# Altium_Designer_schematic.net
KiCad netlist of a schematic drawn in Altium Designer
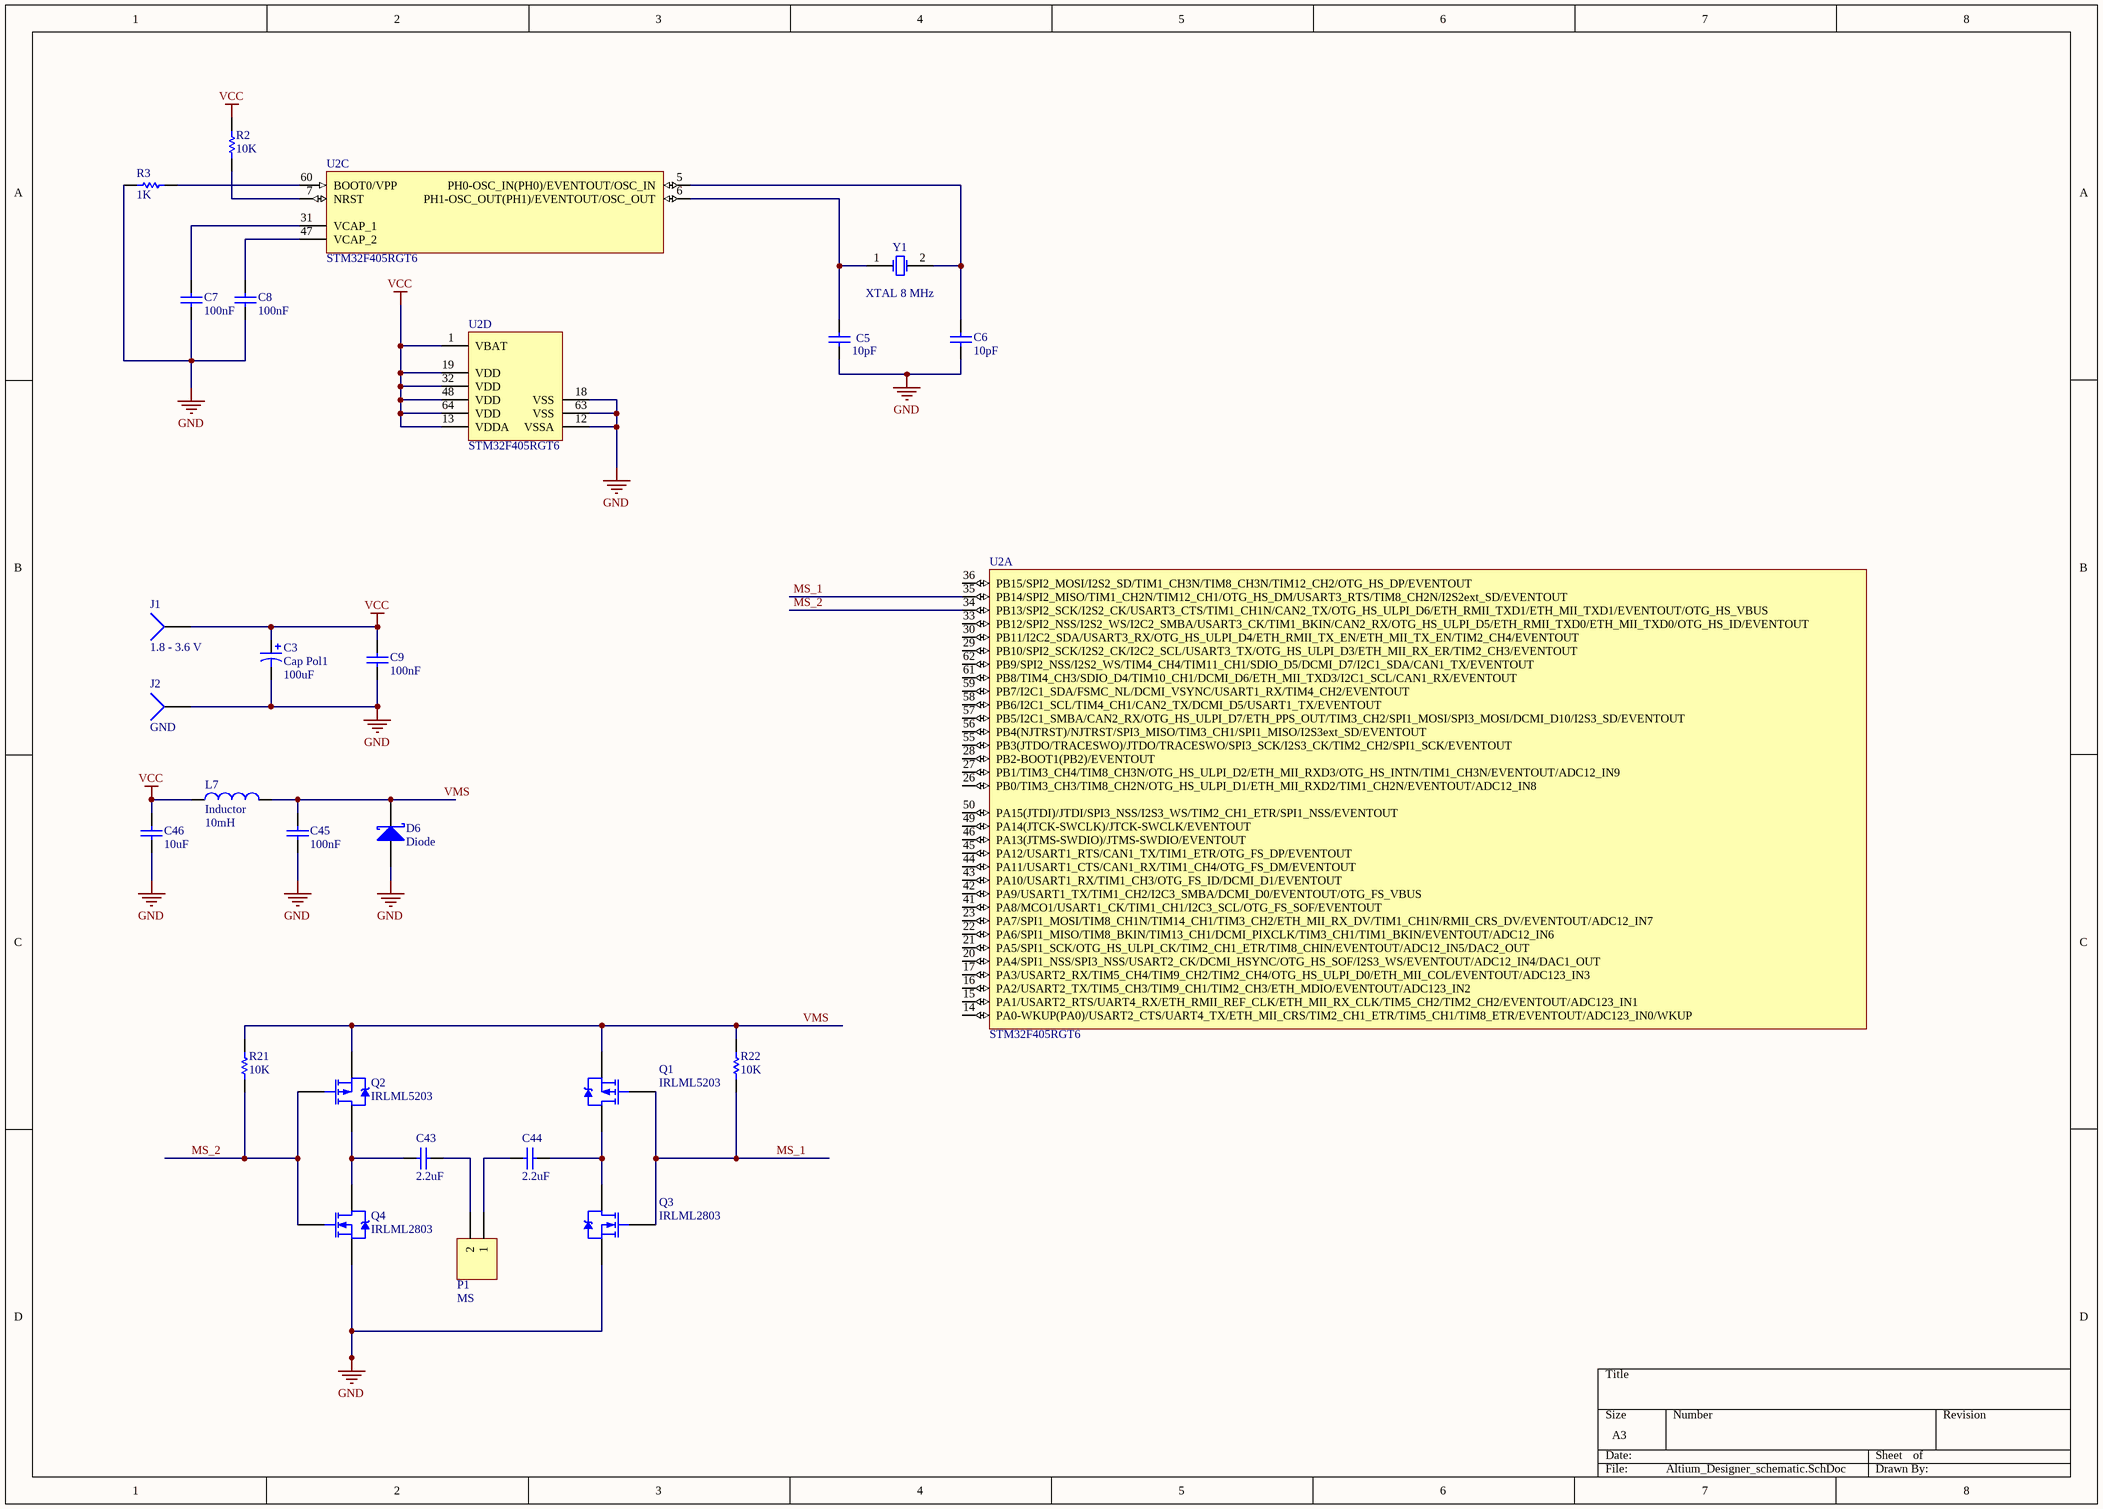
[diagram p0: Altium_Designer_schematic.SchDoc]

(export (version "E")
  (design (tool "Eeschema 10.0.6"))
  (components
    (comp (ref "C3")
      (value "Cap Pol1")
      (footprint "RB7.6-15")
      (description "Polarized Capacitor (Radial)")
      (fields (field (name "ALTIUM_VALUE") "100uF") (field (name "PUBLISHER") "Altium Limited"))
      (libsource (lib "Miscellaneous Devices") (part "Cap Pol1"))
    )
    (comp (ref "C5")
      (value "10pF")
      (footprint "Miscellaneous Devices:1-0805_N")
      (description "Capacitor")
      (fields (field (name "PUBLISHER") "Altium Limited"))
      (libsource (lib "Miscellaneous Devices") (part "Cap"))
    )
    (comp (ref "C6")
      (value "10pF")
      (footprint "Miscellaneous Devices:1-0805_N")
      (description "Capacitor")
      (fields (field (name "PUBLISHER") "Altium Limited"))
      (libsource (lib "Miscellaneous Devices") (part "Cap"))
    )
    (comp (ref "C7")
      (value "100nF")
      (footprint "Miscellaneous Devices:1-0805_N")
      (description "Capacitor")
      (fields (field (name "PUBLISHER") "Altium Limited"))
      (libsource (lib "Miscellaneous Devices") (part "Cap"))
    )
    (comp (ref "C8")
      (value "100nF")
      (footprint "Miscellaneous Devices:1-0805_N")
      (description "Capacitor")
      (fields (field (name "PUBLISHER") "Altium Limited"))
      (libsource (lib "Miscellaneous Devices") (part "Cap"))
    )
    (comp (ref "C9")
      (value "100nF")
      (footprint "Miscellaneous Devices:1-0805_N")
      (description "Capacitor")
      (fields (field (name "PUBLISHER") "Altium Limited"))
      (libsource (lib "Miscellaneous Devices") (part "Cap"))
    )
    (comp (ref "C43")
      (value "2.2uF")
      (footprint "Miscellaneous Devices:1-0805_N")
      (description "Capacitor")
      (fields (field (name "VOLTAGE") "30V") (field (name "PUBLISHER") "Altium Limited"))
      (libsource (lib "Miscellaneous Devices") (part "Cap"))
    )
    (comp (ref "C44")
      (value "2.2uF")
      (footprint "Miscellaneous Devices:1-0805_N")
      (description "Capacitor")
      (fields (field (name "VOLTAGE") "30V") (field (name "PUBLISHER") "Altium Limited"))
      (libsource (lib "Miscellaneous Devices") (part "Cap"))
    )
    (comp (ref "C45")
      (value "100nF")
      (footprint "Miscellaneous Devices:1-0805_N")
      (description "Capacitor")
      (fields (field (name "VOLTAGE") "30V") (field (name "PUBLISHER") "Altium Limited"))
      (libsource (lib "Miscellaneous Devices") (part "Cap"))
    )
    (comp (ref "C46")
      (value "10uF")
      (footprint "Miscellaneous Devices:1-0805_N")
      (description "Capacitor")
      (fields (field (name "VOLTAGE") "30V") (field (name "PUBLISHER") "Altium Limited"))
      (libsource (lib "Miscellaneous Devices") (part "Cap"))
    )
    (comp (ref "D6")
      (value "Diode")
      (footprint "SOT-23_L")
      (description "Silicon RF Schottky Diode for Mixer Applications in the VHF/UHF Range")
      (fields (field (name "PUBLISHER") "Altium Limited"))
      (libsource (lib "Miscellaneous Devices") (part "Diode BAT17"))
    )
    (comp (ref "J1")
      (value "1.8 - 3.6 V")
      (footprint "PIN1")
      (description "Socket")
      (fields (field (name "PUBLISHER") "Altium Limited"))
      (libsource (lib "Miscellaneous Connectors") (part "Socket"))
    )
    (comp (ref "J2")
      (value "GND")
      (footprint "PIN1")
      (description "Socket")
      (fields (field (name "PUBLISHER") "Altium Limited"))
      (libsource (lib "Miscellaneous Connectors") (part "Socket"))
    )
    (comp (ref "L7")
      (value "Inductor")
      (footprint "Miscellaneous Devices:1-0805_N")
      (fields (field (name "ALTIUM_VALUE") "10mH") (field (name "PUBLISHER") "Altium Limited"))
      (libsource (lib "Miscellaneous Devices") (part "Inductor"))
    )
    (comp (ref "P1")
      (value "MS")
      (footprint "HDR1X2")
      (description "Header, 2-Pin")
      (fields (field (name "PUBLISHER") "Altium Limited"))
      (libsource (lib "Miscellaneous Connectors") (part "Header 2"))
    )
    (comp (ref "Q1")
      (value "IRLML5203")
      (footprint "Miscellaneous Devices:SOT23_N")
      (description "P-Channel Power MOSFET")
      (fields (field (name "PUBLISHER") "Altium Limited"))
      (libsource (lib "Miscellaneous Devices") (part "PMOS-2"))
    )
    (comp (ref "Q2")
      (value "IRLML5203")
      (footprint "Miscellaneous Devices:SOT23_N")
      (description "P-Channel Power MOSFET")
      (fields (field (name "PUBLISHER") "Altium Limited"))
      (libsource (lib "Miscellaneous Devices") (part "PMOS-2"))
    )
    (comp (ref "Q3")
      (value "IRLML2803")
      (footprint "Miscellaneous Devices:SOT-23_N")
      (description "N-Channel Power MOSFET")
      (fields (field (name "PUBLISHER") "Altium Limited"))
      (libsource (lib "Miscellaneous Devices") (part "NMOS-2"))
    )
    (comp (ref "Q4")
      (value "IRLML2803")
      (footprint "Miscellaneous Devices:SOT-23_N")
      (description "N-Channel Power MOSFET")
      (fields (field (name "PUBLISHER") "Altium Limited"))
      (libsource (lib "Miscellaneous Devices") (part "NMOS-2"))
    )
    (comp (ref "R2")
      (value "10K")
      (footprint "Miscellaneous Devices:1-0805_N")
      (description "Resistor")
      (fields (field (name "PUBLISHER") "Altium Limited"))
      (libsource (lib "Miscellaneous Devices") (part "Res1"))
    )
    (comp (ref "R3")
      (value "1K")
      (footprint "Miscellaneous Devices:1-0805_N")
      (description "Resistor")
      (fields (field (name "PUBLISHER") "Altium Limited"))
      (libsource (lib "Miscellaneous Devices") (part "Res1"))
    )
    (comp (ref "R21")
      (value "10K")
      (footprint "Miscellaneous Devices:1-0805_N")
      (description "Resistor")
      (fields (field (name "PUBLISHER") "Altium Limited"))
      (libsource (lib "Miscellaneous Devices") (part "Res1"))
    )
    (comp (ref "R22")
      (value "10K")
      (footprint "Miscellaneous Devices:1-0805_N")
      (description "Resistor")
      (fields (field (name "PUBLISHER") "Altium Limited"))
      (libsource (lib "Miscellaneous Devices") (part "Res1"))
    )
    (comp (ref "U2")
      (value "STM32F405RGT6")
      (footprint "TQFP64_N")
      (libsource (lib "") (part "STM32F405RGT6_1"))
    )
    (comp (ref "Y1")
      (value "XTAL 8 MHz")
      (footprint "My_footprint:QUARTZ")
      (description "Crystal Oscillator")
      (fields (field (name "PUBLISHER") "Altium Limited"))
      (libsource (lib "Miscellaneous Devices") (part "XTAL"))
    )
  )
  (nets
    (net (code "1") (name "/MS_1") (class "Default")
      (node (ref "Q1") (pin "3") (pinfunction "G_3") (pintype "passive"))
      (node (ref "Q3") (pin "1") (pinfunction "G_1") (pintype "passive"))
      (node (ref "R22") (pin "1") (pinfunction "1_1") (pintype "passive"))
      (node (ref "U2") (pin "35") (pinfunction "PB14/SPI2_MISO/TIM1_CH2N/TIM12_CH1/OTG_HS_DM/USART3_RTS/TIM8_CH2N/I2S2ext_SD/EVENTOUT_35") (pintype "bidirectional"))
    )
    (net (code "2") (name "/MS_2") (class "Default")
      (node (ref "Q2") (pin "3") (pinfunction "G_3") (pintype "passive"))
      (node (ref "Q4") (pin "1") (pinfunction "G_1") (pintype "passive"))
      (node (ref "R21") (pin "1") (pinfunction "1_1") (pintype "passive"))
      (node (ref "U2") (pin "34") (pinfunction "PB13/SPI2_SCK/I2S2_CK/USART3_CTS/TIM1_CH1N/CAN2_TX/OTG_HS_ULPI_D6/ETH_RMII_TXD1/ETH_MII_TXD1/EVENTOUT/OTG_HS_VBUS_34") (pintype "bidirectional"))
    )
    (net (code "3") (name "/VMS") (class "Default")
      (node (ref "C45") (pin "1") (pinfunction "1_1") (pintype "passive"))
      (node (ref "D6") (pin "3") (pinfunction "K_3") (pintype "passive"))
      (node (ref "L7") (pin "2") (pinfunction "2_2") (pintype "passive"))
      (node (ref "Q1") (pin "2") (pinfunction "S_2") (pintype "passive"))
      (node (ref "Q2") (pin "2") (pinfunction "S_2") (pintype "passive"))
      (node (ref "R21") (pin "2") (pinfunction "2_2") (pintype "passive"))
      (node (ref "R22") (pin "2") (pinfunction "2_2") (pintype "passive"))
    )
    (net (code "4") (name "GND") (class "Default")
      (node (ref "C3") (pin "2") (pinfunction "2_2") (pintype "passive"))
      (node (ref "C45") (pin "2") (pinfunction "2_2") (pintype "passive"))
      (node (ref "C46") (pin "2") (pinfunction "2_2") (pintype "passive"))
      (node (ref "C5") (pin "1") (pinfunction "1_1") (pintype "passive"))
      (node (ref "C6") (pin "1") (pinfunction "1_1") (pintype "passive"))
      (node (ref "C7") (pin "1") (pinfunction "1_1") (pintype "passive"))
      (node (ref "C8") (pin "1") (pinfunction "1_1") (pintype "passive"))
      (node (ref "C9") (pin "1") (pinfunction "1_1") (pintype "passive"))
      (node (ref "D6") (pin "1") (pinfunction "A_1") (pintype "passive"))
      (node (ref "J2") (pin "1") (pinfunction "1_1") (pintype "passive"))
      (node (ref "Q3") (pin "2") (pinfunction "S_2") (pintype "passive"))
      (node (ref "Q4") (pin "2") (pinfunction "S_2") (pintype "passive"))
      (node (ref "R3") (pin "1") (pinfunction "1_1") (pintype "passive"))
      (node (ref "U2") (pin "12") (pinfunction "VSSA_12") (pintype "power_in"))
      (node (ref "U2") (pin "18") (pinfunction "VSS_18") (pintype "power_in"))
      (node (ref "U2") (pin "63") (pinfunction "VSS_63") (pintype "power_in"))
    )
    (net (code "5") (name "Net-(C43-Pad2)") (class "Default")
      (node (ref "C43") (pin "2") (pinfunction "2_2") (pintype "passive"))
      (node (ref "P1") (pin "2") (pinfunction "2_2") (pintype "passive"))
    )
    (net (code "6") (name "Net-(C44-Pad2)") (class "Default")
      (node (ref "C44") (pin "2") (pinfunction "2_2") (pintype "passive"))
      (node (ref "P1") (pin "1") (pinfunction "1_1") (pintype "passive"))
    )
    (net (code "7") (name "Net-(Q1-D)") (class "Default")
      (node (ref "C44") (pin "1") (pinfunction "1_1") (pintype "passive"))
      (node (ref "Q1") (pin "1") (pinfunction "D_1") (pintype "passive"))
      (node (ref "Q3") (pin "3") (pinfunction "D_3") (pintype "passive"))
    )
    (net (code "8") (name "Net-(Q2-D)") (class "Default")
      (node (ref "C43") (pin "1") (pinfunction "1_1") (pintype "passive"))
      (node (ref "Q2") (pin "1") (pinfunction "D_1") (pintype "passive"))
      (node (ref "Q4") (pin "3") (pinfunction "D_3") (pintype "passive"))
    )
    (net (code "9") (name "Net-(U2C-BOOT0{slash}VPP)") (class "Default")
      (node (ref "R3") (pin "2") (pinfunction "2_2") (pintype "passive"))
      (node (ref "U2") (pin "60") (pinfunction "BOOT0/VPP_60") (pintype "input"))
    )
    (net (code "10") (name "Net-(U2C-NRST)") (class "Default")
      (node (ref "R2") (pin "1") (pinfunction "1_1") (pintype "passive"))
      (node (ref "U2") (pin "7") (pinfunction "NRST_7") (pintype "bidirectional"))
    )
    (net (code "11") (name "Net-(U2C-PH0-OSC_IN(PH0){slash}EVENTOUT{slash}OSC_IN)") (class "Default")
      (node (ref "C6") (pin "2") (pinfunction "2_2") (pintype "passive"))
      (node (ref "U2") (pin "5") (pinfunction "PH0-OSC_IN(PH0)/EVENTOUT/OSC_IN_5") (pintype "bidirectional"))
      (node (ref "Y1") (pin "2") (pinfunction "OSC2_2") (pintype "passive"))
    )
    (net (code "12") (name "Net-(U2C-PH1-OSC_OUT(PH1){slash}EVENTOUT{slash}OSC_OUT)") (class "Default")
      (node (ref "C5") (pin "2") (pinfunction "2_2") (pintype "passive"))
      (node (ref "U2") (pin "6") (pinfunction "PH1-OSC_OUT(PH1)/EVENTOUT/OSC_OUT_6") (pintype "bidirectional"))
      (node (ref "Y1") (pin "1") (pinfunction "OSC1_1") (pintype "passive"))
    )
    (net (code "13") (name "Net-(U2C-VCAP_1)") (class "Default")
      (node (ref "C7") (pin "2") (pinfunction "2_2") (pintype "passive"))
      (node (ref "U2") (pin "31") (pinfunction "VCAP_1_31") (pintype "power_in"))
    )
    (net (code "14") (name "Net-(U2C-VCAP_2)") (class "Default")
      (node (ref "C8") (pin "2") (pinfunction "2_2") (pintype "passive"))
      (node (ref "U2") (pin "47") (pinfunction "VCAP_2_47") (pintype "power_in"))
    )
    (net (code "15") (name "VCC") (class "Default")
      (node (ref "C3") (pin "1") (pinfunction "1_1") (pintype "passive"))
      (node (ref "C46") (pin "1") (pinfunction "1_1") (pintype "passive"))
      (node (ref "C9") (pin "2") (pinfunction "2_2") (pintype "passive"))
      (node (ref "J1") (pin "1") (pinfunction "1_1") (pintype "passive"))
      (node (ref "L7") (pin "1") (pinfunction "1_1") (pintype "passive"))
      (node (ref "R2") (pin "2") (pinfunction "2_2") (pintype "passive"))
      (node (ref "U2") (pin "1") (pinfunction "VBAT_1") (pintype "power_in"))
      (node (ref "U2") (pin "13") (pinfunction "VDDA_13") (pintype "power_in"))
      (node (ref "U2") (pin "19") (pinfunction "VDD_19") (pintype "power_in"))
      (node (ref "U2") (pin "32") (pinfunction "VDD_32") (pintype "power_in"))
      (node (ref "U2") (pin "48") (pinfunction "VDD_48") (pintype "power_in"))
      (node (ref "U2") (pin "64") (pinfunction "VDD_64") (pintype "power_in"))
    )
    (net (code "16") (name "unconnected-(U2A-PA0-WKUP(PA0){slash}USART2_CTS{slash}UART4_TX{slash}ETH_MII_CRS{slash}TIM2_CH1_ETR{slash}TIM5_CH1{slash}TIM8_ETR{slash}EVENTOUT{slash}ADC123_IN0{slash}WKUP-Pad14)") (class "Default")
      (node (ref "U2") (pin "14") (pinfunction "PA0-WKUP(PA0)/USART2_CTS/UART4_TX/ETH_MII_CRS/TIM2_CH1_ETR/TIM5_CH1/TIM8_ETR/EVENTOUT/ADC123_IN0/WKUP_14") (pintype "bidirectional"))
    )
    (net (code "17") (name "unconnected-(U2A-PA1{slash}USART2_RTS{slash}UART4_RX{slash}ETH_RMII_REF_CLK{slash}ETH_MII_RX_CLK{slash}TIM5_CH2{slash}TIM2_CH2{slash}EVENTOUT{slash}ADC123_IN1-Pad15)") (class "Default")
      (node (ref "U2") (pin "15") (pinfunction "PA1/USART2_RTS/UART4_RX/ETH_RMII_REF_CLK/ETH_MII_RX_CLK/TIM5_CH2/TIM2_CH2/EVENTOUT/ADC123_IN1_15") (pintype "bidirectional"))
    )
    (net (code "18") (name "unconnected-(U2A-PA2{slash}USART2_TX{slash}TIM5_CH3{slash}TIM9_CH1{slash}TIM2_CH3{slash}ETH_MDIO{slash}EVENTOUT{slash}ADC123_IN2-Pad16)") (class "Default")
      (node (ref "U2") (pin "16") (pinfunction "PA2/USART2_TX/TIM5_CH3/TIM9_CH1/TIM2_CH3/ETH_MDIO/EVENTOUT/ADC123_IN2_16") (pintype "bidirectional"))
    )
    (net (code "19") (name "unconnected-(U2A-PA3{slash}USART2_RX{slash}TIM5_CH4{slash}TIM9_CH2{slash}TIM2_CH4{slash}OTG_HS_ULPI_D0{slash}ETH_MII_COL{slash}EVENTOUT{slash}ADC123_IN3-Pad17)") (class "Default")
      (node (ref "U2") (pin "17") (pinfunction "PA3/USART2_RX/TIM5_CH4/TIM9_CH2/TIM2_CH4/OTG_HS_ULPI_D0/ETH_MII_COL/EVENTOUT/ADC123_IN3_17") (pintype "bidirectional"))
    )
    (net (code "20") (name "unconnected-(U2A-PA4{slash}SPI1_NSS{slash}SPI3_NSS{slash}USART2_CK{slash}DCMI_HSYNC{slash}OTG_HS_SOF{slash}I2S3_WS{slash}EVENTOUT{slash}ADC12_IN4{slash}DAC1_OUT-Pad20)") (class "Default")
      (node (ref "U2") (pin "20") (pinfunction "PA4/SPI1_NSS/SPI3_NSS/USART2_CK/DCMI_HSYNC/OTG_HS_SOF/I2S3_WS/EVENTOUT/ADC12_IN4/DAC1_OUT_20") (pintype "bidirectional"))
    )
    (net (code "21") (name "unconnected-(U2A-PA5{slash}SPI1_SCK{slash}OTG_HS_ULPI_CK{slash}TIM2_CH1_ETR{slash}TIM8_CHIN{slash}EVENTOUT{slash}ADC12_IN5{slash}DAC2_OUT-Pad21)") (class "Default")
      (node (ref "U2") (pin "21") (pinfunction "PA5/SPI1_SCK/OTG_HS_ULPI_CK/TIM2_CH1_ETR/TIM8_CHIN/EVENTOUT/ADC12_IN5/DAC2_OUT_21") (pintype "bidirectional"))
    )
    (net (code "22") (name "unconnected-(U2A-PA6{slash}SPI1_MISO{slash}TIM8_BKIN{slash}TIM13_CH1{slash}DCMI_PIXCLK{slash}TIM3_CH1{slash}TIM1_BKIN{slash}EVENTOUT{slash}ADC12_IN6-Pad22)") (class "Default")
      (node (ref "U2") (pin "22") (pinfunction "PA6/SPI1_MISO/TIM8_BKIN/TIM13_CH1/DCMI_PIXCLK/TIM3_CH1/TIM1_BKIN/EVENTOUT/ADC12_IN6_22") (pintype "bidirectional"))
    )
    (net (code "23") (name "unconnected-(U2A-PA7{slash}SPI1_MOSI{slash}TIM8_CH1N{slash}TIM14_CH1{slash}TIM3_CH2{slash}ETH_MII_RX_DV{slash}TIM1_CH1N{slash}RMII_CRS_DV{slash}EVENTOUT{slash}ADC12_IN7-Pad23)") (class "Default")
      (node (ref "U2") (pin "23") (pinfunction "PA7/SPI1_MOSI/TIM8_CH1N/TIM14_CH1/TIM3_CH2/ETH_MII_RX_DV/TIM1_CH1N/RMII_CRS_DV/EVENTOUT/ADC12_IN7_23") (pintype "bidirectional"))
    )
    (net (code "24") (name "unconnected-(U2A-PA8{slash}MCO1{slash}USART1_CK{slash}TIM1_CH1{slash}I2C3_SCL{slash}OTG_FS_SOF{slash}EVENTOUT-Pad41)") (class "Default")
      (node (ref "U2") (pin "41") (pinfunction "PA8/MCO1/USART1_CK/TIM1_CH1/I2C3_SCL/OTG_FS_SOF/EVENTOUT_41") (pintype "bidirectional"))
    )
    (net (code "25") (name "unconnected-(U2A-PA9{slash}USART1_TX{slash}TIM1_CH2{slash}I2C3_SMBA{slash}DCMI_D0{slash}EVENTOUT{slash}OTG_FS_VBUS-Pad42)") (class "Default")
      (node (ref "U2") (pin "42") (pinfunction "PA9/USART1_TX/TIM1_CH2/I2C3_SMBA/DCMI_D0/EVENTOUT/OTG_FS_VBUS_42") (pintype "bidirectional"))
    )
    (net (code "26") (name "unconnected-(U2A-PA10{slash}USART1_RX{slash}TIM1_CH3{slash}OTG_FS_ID{slash}DCMI_D1{slash}EVENTOUT-Pad43)") (class "Default")
      (node (ref "U2") (pin "43") (pinfunction "PA10/USART1_RX/TIM1_CH3/OTG_FS_ID/DCMI_D1/EVENTOUT_43") (pintype "bidirectional"))
    )
    (net (code "27") (name "unconnected-(U2A-PA11{slash}USART1_CTS{slash}CAN1_RX{slash}TIM1_CH4{slash}OTG_FS_DM{slash}EVENTOUT-Pad44)") (class "Default")
      (node (ref "U2") (pin "44") (pinfunction "PA11/USART1_CTS/CAN1_RX/TIM1_CH4/OTG_FS_DM/EVENTOUT_44") (pintype "bidirectional"))
    )
    (net (code "28") (name "unconnected-(U2A-PA12{slash}USART1_RTS{slash}CAN1_TX{slash}TIM1_ETR{slash}OTG_FS_DP{slash}EVENTOUT-Pad45)") (class "Default")
      (node (ref "U2") (pin "45") (pinfunction "PA12/USART1_RTS/CAN1_TX/TIM1_ETR/OTG_FS_DP/EVENTOUT_45") (pintype "bidirectional"))
    )
    (net (code "29") (name "unconnected-(U2A-PA13(JTMS-SWDIO){slash}JTMS-SWDIO{slash}EVENTOUT-Pad46)") (class "Default")
      (node (ref "U2") (pin "46") (pinfunction "PA13(JTMS-SWDIO)/JTMS-SWDIO/EVENTOUT_46") (pintype "bidirectional"))
    )
    (net (code "30") (name "unconnected-(U2A-PA14(JTCK-SWCLK){slash}JTCK-SWCLK{slash}EVENTOUT-Pad49)") (class "Default")
      (node (ref "U2") (pin "49") (pinfunction "PA14(JTCK-SWCLK)/JTCK-SWCLK/EVENTOUT_49") (pintype "bidirectional"))
    )
    (net (code "31") (name "unconnected-(U2A-PA15(JTDI){slash}JTDI{slash}SPI3_NSS{slash}I2S3_WS{slash}TIM2_CH1_ETR{slash}SPI1_NSS{slash}EVENTOUT-Pad50)") (class "Default")
      (node (ref "U2") (pin "50") (pinfunction "PA15(JTDI)/JTDI/SPI3_NSS/I2S3_WS/TIM2_CH1_ETR/SPI1_NSS/EVENTOUT_50") (pintype "bidirectional"))
    )
    (net (code "32") (name "unconnected-(U2A-PB0{slash}TIM3_CH3{slash}TIM8_CH2N{slash}OTG_HS_ULPI_D1{slash}ETH_MII_RXD2{slash}TIM1_CH2N{slash}EVENTOUT{slash}ADC12_IN8-Pad26)") (class "Default")
      (node (ref "U2") (pin "26") (pinfunction "PB0/TIM3_CH3/TIM8_CH2N/OTG_HS_ULPI_D1/ETH_MII_RXD2/TIM1_CH2N/EVENTOUT/ADC12_IN8_26") (pintype "bidirectional"))
    )
    (net (code "33") (name "unconnected-(U2A-PB1{slash}TIM3_CH4{slash}TIM8_CH3N{slash}OTG_HS_ULPI_D2{slash}ETH_MII_RXD3{slash}OTG_HS_INTN{slash}TIM1_CH3N{slash}EVENTOUT{slash}ADC12_IN9-Pad27)") (class "Default")
      (node (ref "U2") (pin "27") (pinfunction "PB1/TIM3_CH4/TIM8_CH3N/OTG_HS_ULPI_D2/ETH_MII_RXD3/OTG_HS_INTN/TIM1_CH3N/EVENTOUT/ADC12_IN9_27") (pintype "bidirectional"))
    )
    (net (code "34") (name "unconnected-(U2A-PB2-BOOT1(PB2){slash}EVENTOUT-Pad28)") (class "Default")
      (node (ref "U2") (pin "28") (pinfunction "PB2-BOOT1(PB2)/EVENTOUT_28") (pintype "bidirectional"))
    )
    (net (code "35") (name "unconnected-(U2A-PB3(JTDO{slash}TRACESWO){slash}JTDO{slash}TRACESWO{slash}SPI3_SCK{slash}I2S3_CK{slash}TIM2_CH2{slash}SPI1_SCK{slash}EVENTOUT-Pad55)") (class "Default")
      (node (ref "U2") (pin "55") (pinfunction "PB3(JTDO/TRACESWO)/JTDO/TRACESWO/SPI3_SCK/I2S3_CK/TIM2_CH2/SPI1_SCK/EVENTOUT_55") (pintype "bidirectional"))
    )
    (net (code "36") (name "unconnected-(U2A-PB4(NJTRST){slash}NJTRST{slash}SPI3_MISO{slash}TIM3_CH1{slash}SPI1_MISO{slash}I2S3ext_SD{slash}EVENTOUT-Pad56)") (class "Default")
      (node (ref "U2") (pin "56") (pinfunction "PB4(NJTRST)/NJTRST/SPI3_MISO/TIM3_CH1/SPI1_MISO/I2S3ext_SD/EVENTOUT_56") (pintype "bidirectional"))
    )
    (net (code "37") (name "unconnected-(U2A-PB5{slash}I2C1_SMBA{slash}CAN2_RX{slash}OTG_HS_ULPI_D7{slash}ETH_PPS_OUT{slash}TIM3_CH2{slash}SPI1_MOSI{slash}SPI3_MOSI{slash}DCMI_D10{slash}I2S3_SD{slash}EVENTOUT-Pad57)") (class "Default")
      (node (ref "U2") (pin "57") (pinfunction "PB5/I2C1_SMBA/CAN2_RX/OTG_HS_ULPI_D7/ETH_PPS_OUT/TIM3_CH2/SPI1_MOSI/SPI3_MOSI/DCMI_D10/I2S3_SD/EVENTOUT_57") (pintype "bidirectional"))
    )
    (net (code "38") (name "unconnected-(U2A-PB6{slash}I2C1_SCL{slash}TIM4_CH1{slash}CAN2_TX{slash}DCMI_D5{slash}USART1_TX{slash}EVENTOUT-Pad58)") (class "Default")
      (node (ref "U2") (pin "58") (pinfunction "PB6/I2C1_SCL/TIM4_CH1/CAN2_TX/DCMI_D5/USART1_TX/EVENTOUT_58") (pintype "bidirectional"))
    )
    (net (code "39") (name "unconnected-(U2A-PB7{slash}I2C1_SDA{slash}FSMC_NL{slash}DCMI_VSYNC{slash}USART1_RX{slash}TIM4_CH2{slash}EVENTOUT-Pad59)") (class "Default")
      (node (ref "U2") (pin "59") (pinfunction "PB7/I2C1_SDA/FSMC_NL/DCMI_VSYNC/USART1_RX/TIM4_CH2/EVENTOUT_59") (pintype "bidirectional"))
    )
    (net (code "40") (name "unconnected-(U2A-PB8{slash}TIM4_CH3{slash}SDIO_D4{slash}TIM10_CH1{slash}DCMI_D6{slash}ETH_MII_TXD3{slash}I2C1_SCL{slash}CAN1_RX{slash}EVENTOUT-Pad61)") (class "Default")
      (node (ref "U2") (pin "61") (pinfunction "PB8/TIM4_CH3/SDIO_D4/TIM10_CH1/DCMI_D6/ETH_MII_TXD3/I2C1_SCL/CAN1_RX/EVENTOUT_61") (pintype "bidirectional"))
    )
    (net (code "41") (name "unconnected-(U2A-PB9{slash}SPI2_NSS{slash}I2S2_WS{slash}TIM4_CH4{slash}TIM11_CH1{slash}SDIO_D5{slash}DCMI_D7{slash}I2C1_SDA{slash}CAN1_TX{slash}EVENTOUT-Pad62)") (class "Default")
      (node (ref "U2") (pin "62") (pinfunction "PB9/SPI2_NSS/I2S2_WS/TIM4_CH4/TIM11_CH1/SDIO_D5/DCMI_D7/I2C1_SDA/CAN1_TX/EVENTOUT_62") (pintype "bidirectional"))
    )
    (net (code "42") (name "unconnected-(U2A-PB10{slash}SPI2_SCK{slash}I2S2_CK{slash}I2C2_SCL{slash}USART3_TX{slash}OTG_HS_ULPI_D3{slash}ETH_MII_RX_ER{slash}TIM2_CH3{slash}EVENTOUT-Pad29)") (class "Default")
      (node (ref "U2") (pin "29") (pinfunction "PB10/SPI2_SCK/I2S2_CK/I2C2_SCL/USART3_TX/OTG_HS_ULPI_D3/ETH_MII_RX_ER/TIM2_CH3/EVENTOUT_29") (pintype "bidirectional"))
    )
    (net (code "43") (name "unconnected-(U2A-PB11{slash}I2C2_SDA{slash}USART3_RX{slash}OTG_HS_ULPI_D4{slash}ETH_RMII_TX_EN{slash}ETH_MII_TX_EN{slash}TIM2_CH4{slash}EVENTOUT-Pad30)") (class "Default")
      (node (ref "U2") (pin "30") (pinfunction "PB11/I2C2_SDA/USART3_RX/OTG_HS_ULPI_D4/ETH_RMII_TX_EN/ETH_MII_TX_EN/TIM2_CH4/EVENTOUT_30") (pintype "bidirectional"))
    )
    (net (code "44") (name "unconnected-(U2A-PB12{slash}SPI2_NSS{slash}I2S2_WS{slash}I2C2_SMBA{slash}USART3_CK{slash}TIM1_BKIN{slash}CAN2_RX{slash}OTG_HS_ULPI_D5{slash}ETH_RMII_TXD0{slash}ETH_MII_TXD0{slash}OTG_HS_ID{slash}EVENTOUT-Pad33)") (class "Default")
      (node (ref "U2") (pin "33") (pinfunction "PB12/SPI2_NSS/I2S2_WS/I2C2_SMBA/USART3_CK/TIM1_BKIN/CAN2_RX/OTG_HS_ULPI_D5/ETH_RMII_TXD0/ETH_MII_TXD0/OTG_HS_ID/EVENTOUT_33") (pintype "bidirectional"))
    )
    (net (code "45") (name "unconnected-(U2A-PB15{slash}SPI2_MOSI{slash}I2S2_SD{slash}TIM1_CH3N{slash}TIM8_CH3N{slash}TIM12_CH2{slash}OTG_HS_DP{slash}EVENTOUT-Pad36)") (class "Default")
      (node (ref "U2") (pin "36") (pinfunction "PB15/SPI2_MOSI/I2S2_SD/TIM1_CH3N/TIM8_CH3N/TIM12_CH2/OTG_HS_DP/EVENTOUT_36") (pintype "bidirectional"))
    )
  )
)
